# SparkFun_Mega_Pro_Mini-3_3V.net
KiCad netlist of a schematic drawn in EAGLE
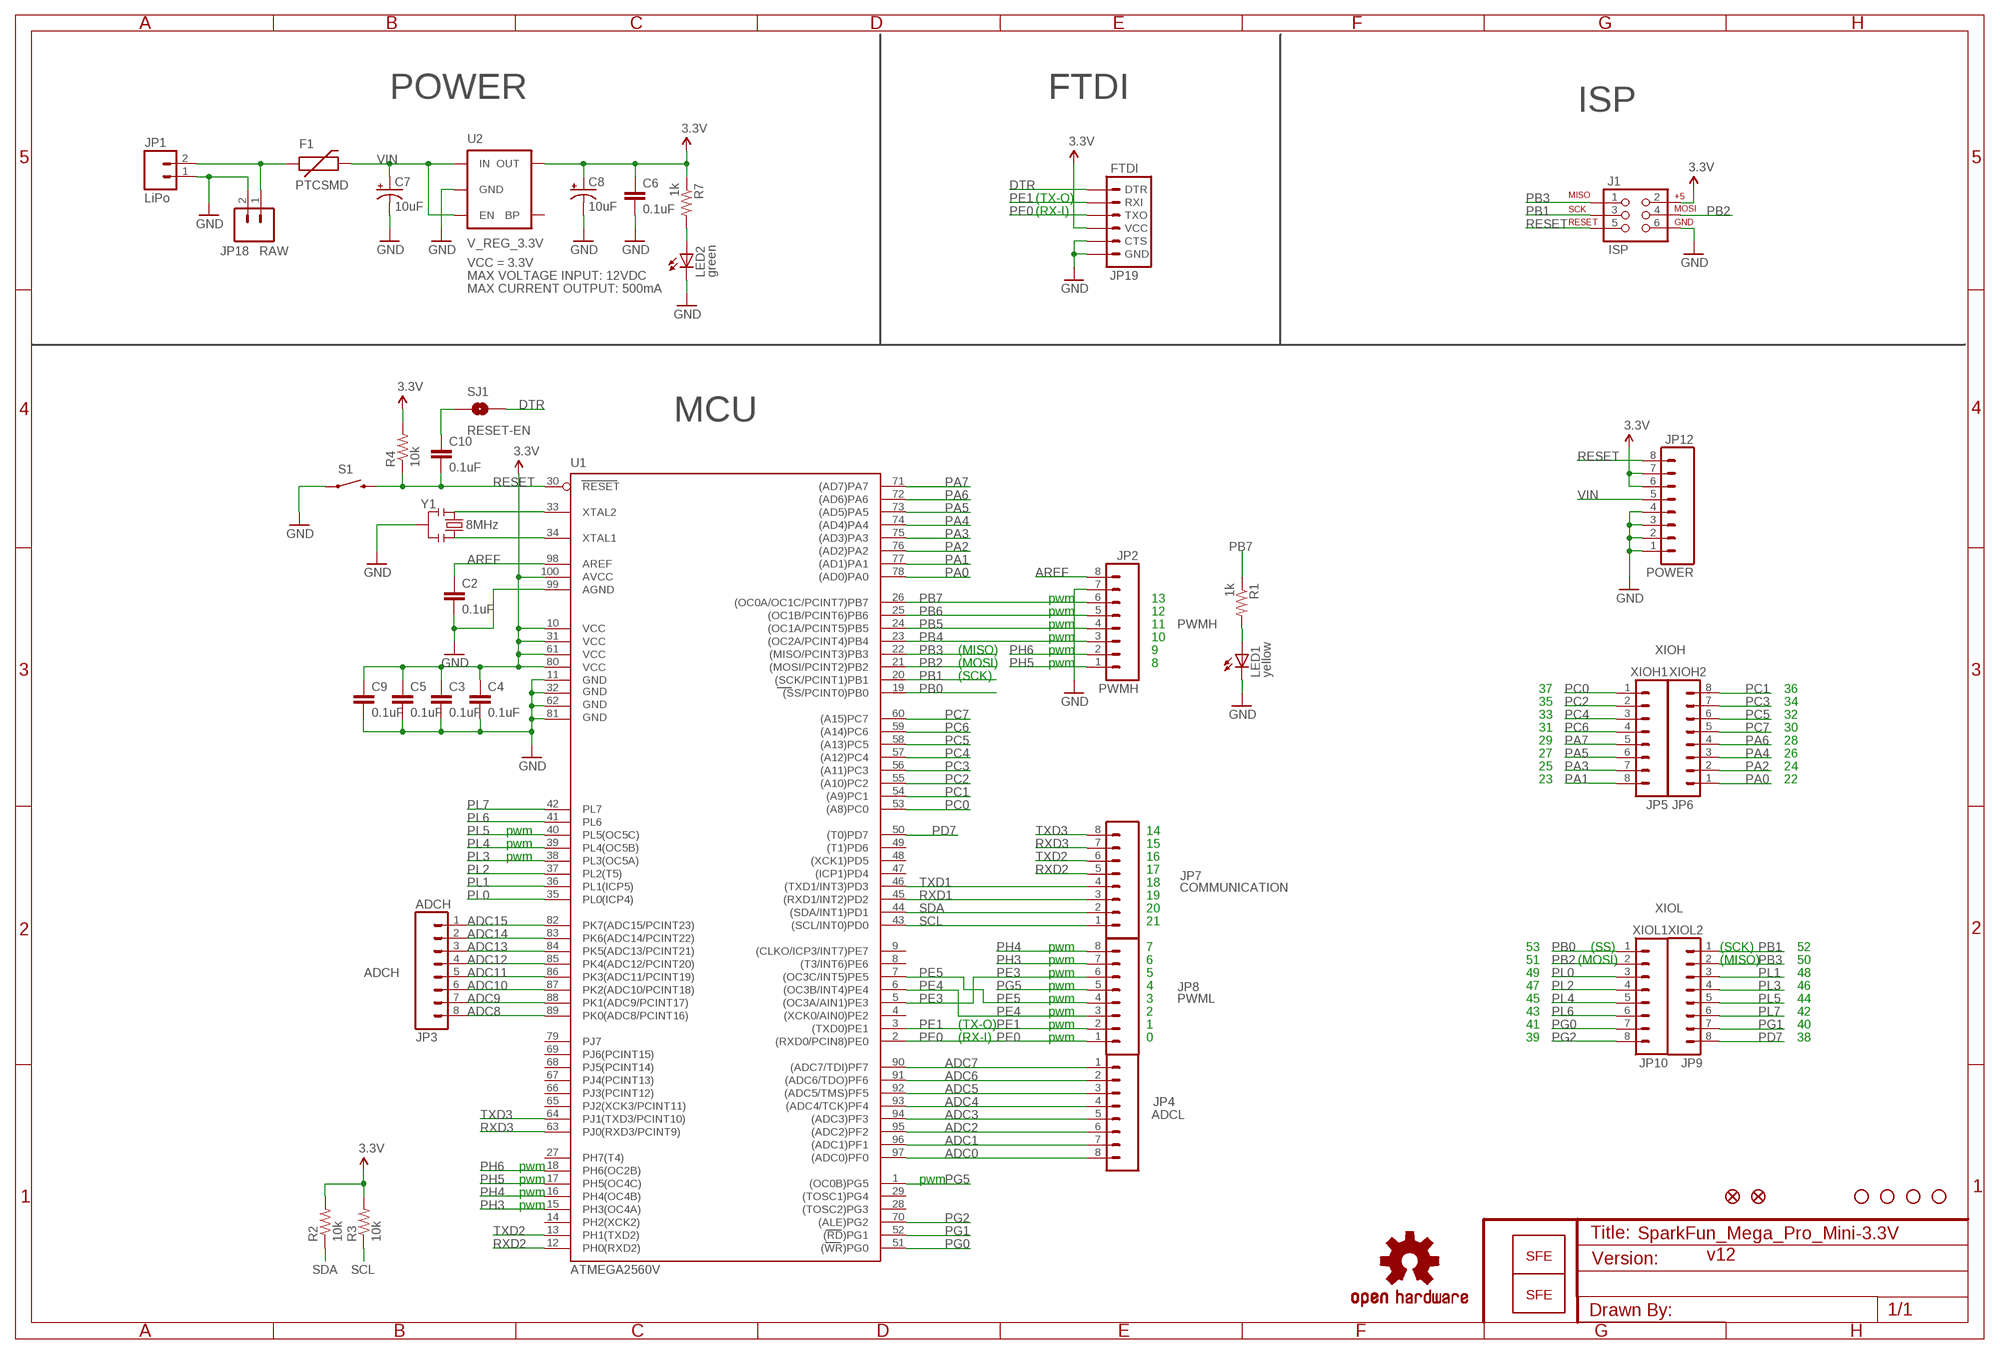
[diagram p0: schematic, sheet 1]

(export (version "E")
  (design (tool "Eeschema 10.0.6"))
  (components
    (comp (ref "C2")
      (value "0.1uF")
      (footprint "eagle-import:0402-CAP")
      (libsource (lib "eagle-import") (part "CAP0402-CAP"))
    )
    (comp (ref "C3")
      (value "0.1uF")
      (footprint "eagle-import:0402-CAP")
      (libsource (lib "eagle-import") (part "CAP0402-CAP"))
    )
    (comp (ref "C4")
      (value "0.1uF")
      (footprint "eagle-import:0402-CAP")
      (libsource (lib "eagle-import") (part "CAP0402-CAP"))
    )
    (comp (ref "C5")
      (value "0.1uF")
      (footprint "eagle-import:0402-CAP")
      (libsource (lib "eagle-import") (part "CAP0402-CAP"))
    )
    (comp (ref "C6")
      (value "0.1uF")
      (footprint "eagle-import:0402-CAP")
      (libsource (lib "eagle-import") (part "CAP0402-CAP"))
    )
    (comp (ref "C7")
      (value "10uF")
      (footprint "eagle-import:EIA3216")
      (libsource (lib "eagle-import") (part "CAP_POL1206"))
    )
    (comp (ref "C8")
      (value "10uF")
      (footprint "eagle-import:EIA3216")
      (libsource (lib "eagle-import") (part "CAP_POL1206"))
    )
    (comp (ref "C9")
      (value "0.1uF")
      (footprint "eagle-import:0402-CAP")
      (libsource (lib "eagle-import") (part "CAP0402-CAP"))
    )
    (comp (ref "C10")
      (value "0.1uF")
      (footprint "eagle-import:0402-CAP")
      (libsource (lib "eagle-import") (part "CAP0402-CAP"))
    )
    (comp (ref "F1")
      (value "PTCSMD")
      (footprint "eagle-import:PTC-1206")
      (libsource (lib "eagle-import") (part "PTCSMD"))
    )
    (comp (ref "J1")
      (value "ISP")
      (footprint "eagle-import:2X3")
      (libsource (lib "eagle-import") (part "AVR_SPI_PRG_6PTH"))
    )
    (comp (ref "JP1")
      (value "LiPo")
      (footprint "eagle-import:JST-2-SMD")
      (libsource (lib "eagle-import") (part "M02-JST-2MM-SMT"))
    )
    (comp (ref "JP2")
      (value "PWMH")
      (footprint "eagle-import:BM08B-SRSS-TB")
      (libsource (lib "eagle-import") (part "M08BM08B-SRSS-TB"))
    )
    (comp (ref "JP3")
      (value "ADCH")
      (footprint "eagle-import:BM08B-SRSS-TB")
      (libsource (lib "eagle-import") (part "M08BM08B-SRSS-TB"))
    )
    (comp (ref "JP4")
      (value "ADCL")
      (footprint "eagle-import:BM08B-SRSS-TB")
      (libsource (lib "eagle-import") (part "M08BM08B-SRSS-TB"))
    )
    (comp (ref "JP5")
      (value "XIOH1")
      (footprint "eagle-import:BM08B-SRSS-TB")
      (libsource (lib "eagle-import") (part "M08BM08B-SRSS-TB"))
    )
    (comp (ref "JP6")
      (value "XIOH2")
      (footprint "eagle-import:BM08B-SRSS-TB")
      (libsource (lib "eagle-import") (part "M08BM08B-SRSS-TB"))
    )
    (comp (ref "JP7")
      (value "COMM")
      (footprint "eagle-import:BM08B-SRSS-TB")
      (libsource (lib "eagle-import") (part "M08BM08B-SRSS-TB"))
    )
    (comp (ref "JP8")
      (value "PWML")
      (footprint "eagle-import:BM08B-SRSS-TB")
      (libsource (lib "eagle-import") (part "M08BM08B-SRSS-TB"))
    )
    (comp (ref "JP9")
      (value "XIOL2")
      (footprint "eagle-import:BM08B-SRSS-TB")
      (libsource (lib "eagle-import") (part "M08BM08B-SRSS-TB"))
    )
    (comp (ref "JP10")
      (value "XIOL1")
      (footprint "eagle-import:BM08B-SRSS-TB")
      (libsource (lib "eagle-import") (part "M08BM08B-SRSS-TB"))
    )
    (comp (ref "JP11")
      (value "STAND-OFF")
      (footprint "eagle-import:STAND-OFF")
      (libsource (lib "eagle-import") (part "STAND-OFF"))
    )
    (comp (ref "JP12")
      (value "POWER")
      (footprint "eagle-import:BM08B-SRSS-TB")
      (libsource (lib "eagle-import") (part "M08BM08B-SRSS-TB"))
    )
    (comp (ref "JP13")
      (value "STAND-OFF")
      (footprint "eagle-import:STAND-OFF")
      (libsource (lib "eagle-import") (part "STAND-OFF"))
    )
    (comp (ref "JP14")
      (value "STAND-OFF")
      (footprint "eagle-import:STAND-OFF")
      (libsource (lib "eagle-import") (part "STAND-OFF"))
    )
    (comp (ref "JP15")
      (value "STAND-OFF")
      (footprint "eagle-import:STAND-OFF")
      (libsource (lib "eagle-import") (part "STAND-OFF"))
    )
    (comp (ref "JP16")
      (value "LOGO-SFENEW")
      (footprint "eagle-import:SFE-NEW-WEBLOGO")
      (libsource (lib "eagle-import") (part "LOGO-SFENEW"))
    )
    (comp (ref "JP17")
      (value "LOGO-SFESK")
      (footprint "eagle-import:SFE-LOGO-FLAME")
      (libsource (lib "eagle-import") (part "LOGO-SFESK"))
    )
    (comp (ref "JP18")
      (value "RAW")
      (footprint "eagle-import:1X02")
      (libsource (lib "eagle-import") (part "M02PTH"))
    )
    (comp (ref "JP19")
      (value "FTDI")
      (footprint "eagle-import:1X06-SMD")
      (libsource (lib "eagle-import") (part "ARDUINO_SERIAL_PROGRAMSMD"))
    )
    (comp (ref "JP20")
      (value "FIDUCIAL1X2.5")
      (footprint "eagle-import:FIDUCIAL-1X2.5")
      (libsource (lib "eagle-import") (part "FIDUCIAL1X2.5"))
    )
    (comp (ref "JP21")
      (value "FIDUCIAL1X2.5")
      (footprint "eagle-import:FIDUCIAL-1X2.5")
      (libsource (lib "eagle-import") (part "FIDUCIAL1X2.5"))
    )
    (comp (ref "LED1")
      (value "yellow")
      (footprint "eagle-import:LED-0603")
      (libsource (lib "eagle-import") (part "LED0603"))
    )
    (comp (ref "LED2")
      (value "green")
      (footprint "eagle-import:LED-0603")
      (libsource (lib "eagle-import") (part "LED0603"))
    )
    (comp (ref "R1")
      (value "1k")
      (footprint "eagle-import:0402-RES")
      (libsource (lib "eagle-import") (part "RESISTOR0402-RES"))
    )
    (comp (ref "R2")
      (value "10k")
      (footprint "eagle-import:0402-RES")
      (libsource (lib "eagle-import") (part "RESISTOR0402-RES"))
    )
    (comp (ref "R3")
      (value "10k")
      (footprint "eagle-import:0402-RES")
      (libsource (lib "eagle-import") (part "RESISTOR0402-RES"))
    )
    (comp (ref "R4")
      (value "10k")
      (footprint "eagle-import:0402-RES")
      (libsource (lib "eagle-import") (part "RESISTOR0402-RES"))
    )
    (comp (ref "R7")
      (value "1k")
      (footprint "eagle-import:0402-RES")
      (libsource (lib "eagle-import") (part "RESISTOR0402-RES"))
    )
    (comp (ref "S1")
      (value "SWITCH-MOMENTARY-2SMD")
      (footprint "eagle-import:TACTILE_SWITCH_SMD")
      (libsource (lib "eagle-import") (part "SWITCH-MOMENTARY-2SMD"))
    )
    (comp (ref "SJ1")
      (value "RESET-EN")
      (footprint "eagle-import:SJ_2S")
      (libsource (lib "eagle-import") (part "SOLDERJUMPERNC"))
    )
    (comp (ref "U$9")
      (value "OSHW-LOGOL")
      (footprint "eagle-import:OSHW-LOGO-L")
      (libsource (lib "eagle-import") (part "OSHW-LOGOL"))
    )
    (comp (ref "U1")
      (value "ATMEGA2560AU")
      (footprint "eagle-import:TQFP100")
      (libsource (lib "eagle-import") (part "ATMEGA2560AU"))
    )
    (comp (ref "U2")
      (value "V_REG_3.3V")
      (footprint "eagle-import:SOT23-5")
      (libsource (lib "eagle-import") (part "V_REG_LDOSMD"))
    )
    (comp (ref "Y1")
      (value "RESONATORSMD")
      (footprint "eagle-import:RESONATOR-SMD")
      (libsource (lib "eagle-import") (part "RESONATORSMD"))
    )
  )
  (nets
    (net (code "1") (name "/ADC0") (class "Default")
      (node (ref "JP4") (pin "8") (pinfunction "8_8") (pintype "passive"))
      (node (ref "U1") (pin "97") (pinfunction "(ADC0)PF0_97") (pintype "bidirectional"))
    )
    (net (code "2") (name "/ADC1") (class "Default")
      (node (ref "JP4") (pin "7") (pinfunction "7_7") (pintype "passive"))
      (node (ref "U1") (pin "96") (pinfunction "(ADC1)PF1_96") (pintype "bidirectional"))
    )
    (net (code "3") (name "/ADC2") (class "Default")
      (node (ref "JP4") (pin "6") (pinfunction "6_6") (pintype "passive"))
      (node (ref "U1") (pin "95") (pinfunction "(ADC2)PF2_95") (pintype "bidirectional"))
    )
    (net (code "4") (name "/ADC3") (class "Default")
      (node (ref "JP4") (pin "5") (pinfunction "5_5") (pintype "passive"))
      (node (ref "U1") (pin "94") (pinfunction "(ADC3)PF3_94") (pintype "bidirectional"))
    )
    (net (code "5") (name "/ADC4") (class "Default")
      (node (ref "JP4") (pin "4") (pinfunction "4_4") (pintype "passive"))
      (node (ref "U1") (pin "93") (pinfunction "(ADC4/TCK)PF4_93") (pintype "bidirectional"))
    )
    (net (code "6") (name "/ADC5") (class "Default")
      (node (ref "JP4") (pin "3") (pinfunction "3_3") (pintype "passive"))
      (node (ref "U1") (pin "92") (pinfunction "(ADC5/TMS)PF5_92") (pintype "bidirectional"))
    )
    (net (code "7") (name "/ADC6") (class "Default")
      (node (ref "JP4") (pin "2") (pinfunction "2_2") (pintype "passive"))
      (node (ref "U1") (pin "91") (pinfunction "(ADC6/TDO)PF6_91") (pintype "bidirectional"))
    )
    (net (code "8") (name "/ADC7") (class "Default")
      (node (ref "JP4") (pin "1") (pinfunction "1_1") (pintype "passive"))
      (node (ref "U1") (pin "90") (pinfunction "(ADC7/TDI)PF7_90") (pintype "bidirectional"))
    )
    (net (code "9") (name "/ADC8") (class "Default")
      (node (ref "JP3") (pin "8") (pinfunction "8_8") (pintype "passive"))
      (node (ref "U1") (pin "89") (pinfunction "PK0(ADC8/PCINT16)_89") (pintype "bidirectional"))
    )
    (net (code "10") (name "/ADC9") (class "Default")
      (node (ref "JP3") (pin "7") (pinfunction "7_7") (pintype "passive"))
      (node (ref "U1") (pin "88") (pinfunction "PK1(ADC9/PCINT17)_88") (pintype "bidirectional"))
    )
    (net (code "11") (name "/ADC10") (class "Default")
      (node (ref "JP3") (pin "6") (pinfunction "6_6") (pintype "passive"))
      (node (ref "U1") (pin "87") (pinfunction "PK2(ADC10/PCINT18)_87") (pintype "bidirectional"))
    )
    (net (code "12") (name "/ADC11") (class "Default")
      (node (ref "JP3") (pin "5") (pinfunction "5_5") (pintype "passive"))
      (node (ref "U1") (pin "86") (pinfunction "PK3(ADC11/PCINT19)_86") (pintype "bidirectional"))
    )
    (net (code "13") (name "/ADC12") (class "Default")
      (node (ref "JP3") (pin "4") (pinfunction "4_4") (pintype "passive"))
      (node (ref "U1") (pin "85") (pinfunction "PK4(ADC12/PCINT20)_85") (pintype "bidirectional"))
    )
    (net (code "14") (name "/ADC13") (class "Default")
      (node (ref "JP3") (pin "3") (pinfunction "3_3") (pintype "passive"))
      (node (ref "U1") (pin "84") (pinfunction "PK5(ADC13/PCINT21)_84") (pintype "bidirectional"))
    )
    (net (code "15") (name "/ADC14") (class "Default")
      (node (ref "JP3") (pin "2") (pinfunction "2_2") (pintype "passive"))
      (node (ref "U1") (pin "83") (pinfunction "PK6(ADC14/PCINT22)_83") (pintype "bidirectional"))
    )
    (net (code "16") (name "/ADC15") (class "Default")
      (node (ref "JP3") (pin "1") (pinfunction "1_1") (pintype "passive"))
      (node (ref "U1") (pin "82") (pinfunction "PK7(ADC15/PCINT23)_82") (pintype "bidirectional"))
    )
    (net (code "17") (name "/AREF") (class "Default")
      (node (ref "C2") (pin "1") (pinfunction "1_1") (pintype "passive"))
      (node (ref "JP2") (pin "8") (pinfunction "8_8") (pintype "passive"))
      (node (ref "U1") (pin "98") (pinfunction "AREF_98") (pintype "bidirectional"))
    )
    (net (code "18") (name "/DTR") (class "Default")
      (node (ref "JP19") (pin "1") (pinfunction "DTR_1") (pintype "passive"))
      (node (ref "SJ1") (pin "2") (pinfunction "2_2") (pintype "passive"))
    )
    (net (code "19") (name "/PA0") (class "Default")
      (node (ref "JP6") (pin "1") (pinfunction "1_1") (pintype "passive"))
      (node (ref "U1") (pin "78") (pinfunction "(AD0)PA0_78") (pintype "bidirectional"))
    )
    (net (code "20") (name "/PA1") (class "Default")
      (node (ref "JP5") (pin "8") (pinfunction "8_8") (pintype "passive"))
      (node (ref "U1") (pin "77") (pinfunction "(AD1)PA1_77") (pintype "bidirectional"))
    )
    (net (code "21") (name "/PA2") (class "Default")
      (node (ref "JP6") (pin "2") (pinfunction "2_2") (pintype "passive"))
      (node (ref "U1") (pin "76") (pinfunction "(AD2)PA2_76") (pintype "bidirectional"))
    )
    (net (code "22") (name "/PA3") (class "Default")
      (node (ref "JP5") (pin "7") (pinfunction "7_7") (pintype "passive"))
      (node (ref "U1") (pin "75") (pinfunction "(AD3)PA3_75") (pintype "bidirectional"))
    )
    (net (code "23") (name "/PA4") (class "Default")
      (node (ref "JP6") (pin "3") (pinfunction "3_3") (pintype "passive"))
      (node (ref "U1") (pin "74") (pinfunction "(AD4)PA4_74") (pintype "bidirectional"))
    )
    (net (code "24") (name "/PA5") (class "Default")
      (node (ref "JP5") (pin "6") (pinfunction "6_6") (pintype "passive"))
      (node (ref "U1") (pin "73") (pinfunction "(AD5)PA5_73") (pintype "bidirectional"))
    )
    (net (code "25") (name "/PA6") (class "Default")
      (node (ref "JP6") (pin "4") (pinfunction "4_4") (pintype "passive"))
      (node (ref "U1") (pin "72") (pinfunction "(AD6)PA6_72") (pintype "bidirectional"))
    )
    (net (code "26") (name "/PA7") (class "Default")
      (node (ref "JP5") (pin "5") (pinfunction "5_5") (pintype "passive"))
      (node (ref "U1") (pin "71") (pinfunction "(AD7)PA7_71") (pintype "bidirectional"))
    )
    (net (code "27") (name "/PB0") (class "Default")
      (node (ref "JP10") (pin "1") (pinfunction "1_1") (pintype "passive"))
      (node (ref "U1") (pin "19") (pinfunction "(SS/PCINT0)PB0_19") (pintype "bidirectional"))
    )
    (net (code "28") (name "/PB1") (class "Default")
      (node (ref "J1") (pin "3") (pinfunction "3_3") (pintype "passive"))
      (node (ref "JP9") (pin "1") (pinfunction "1_1") (pintype "passive"))
      (node (ref "U1") (pin "20") (pinfunction "(SCK/PCINT1)PB1_20") (pintype "bidirectional"))
    )
    (net (code "29") (name "/PB2") (class "Default")
      (node (ref "J1") (pin "4") (pinfunction "4_4") (pintype "passive"))
      (node (ref "JP10") (pin "2") (pinfunction "2_2") (pintype "passive"))
      (node (ref "U1") (pin "21") (pinfunction "(MOSI/PCINT2)PB2_21") (pintype "bidirectional"))
    )
    (net (code "30") (name "/PB3") (class "Default")
      (node (ref "J1") (pin "1") (pinfunction "1_1") (pintype "passive"))
      (node (ref "JP9") (pin "2") (pinfunction "2_2") (pintype "passive"))
      (node (ref "U1") (pin "22") (pinfunction "(MISO/PCINT3)PB3_22") (pintype "bidirectional"))
    )
    (net (code "31") (name "/PB4") (class "Default")
      (node (ref "JP2") (pin "3") (pinfunction "3_3") (pintype "passive"))
      (node (ref "U1") (pin "23") (pinfunction "(OC2A/PCINT4)PB4_23") (pintype "bidirectional"))
    )
    (net (code "32") (name "/PB5") (class "Default")
      (node (ref "JP2") (pin "4") (pinfunction "4_4") (pintype "passive"))
      (node (ref "U1") (pin "24") (pinfunction "(OC1A/PCINT5)PB5_24") (pintype "bidirectional"))
    )
    (net (code "33") (name "/PB6") (class "Default")
      (node (ref "JP2") (pin "5") (pinfunction "5_5") (pintype "passive"))
      (node (ref "U1") (pin "25") (pinfunction "(OC1B/PCINT6)PB6_25") (pintype "bidirectional"))
    )
    (net (code "34") (name "/PB7") (class "Default")
      (node (ref "JP2") (pin "6") (pinfunction "6_6") (pintype "passive"))
      (node (ref "R1") (pin "1") (pinfunction "1_1") (pintype "passive"))
      (node (ref "U1") (pin "26") (pinfunction "(OC0A/OC1C/PCINT7)PB7_26") (pintype "bidirectional"))
    )
    (net (code "35") (name "/PC0") (class "Default")
      (node (ref "JP5") (pin "1") (pinfunction "1_1") (pintype "passive"))
      (node (ref "U1") (pin "53") (pinfunction "(A8)PC0_53") (pintype "bidirectional"))
    )
    (net (code "36") (name "/PC1") (class "Default")
      (node (ref "JP6") (pin "8") (pinfunction "8_8") (pintype "passive"))
      (node (ref "U1") (pin "54") (pinfunction "(A9)PC1_54") (pintype "bidirectional"))
    )
    (net (code "37") (name "/PC2") (class "Default")
      (node (ref "JP5") (pin "2") (pinfunction "2_2") (pintype "passive"))
      (node (ref "U1") (pin "55") (pinfunction "(A10)PC2_55") (pintype "bidirectional"))
    )
    (net (code "38") (name "/PC3") (class "Default")
      (node (ref "JP6") (pin "7") (pinfunction "7_7") (pintype "passive"))
      (node (ref "U1") (pin "56") (pinfunction "(A11)PC3_56") (pintype "bidirectional"))
    )
    (net (code "39") (name "/PC4") (class "Default")
      (node (ref "JP5") (pin "3") (pinfunction "3_3") (pintype "passive"))
      (node (ref "U1") (pin "57") (pinfunction "(A12)PC4_57") (pintype "bidirectional"))
    )
    (net (code "40") (name "/PC5") (class "Default")
      (node (ref "JP6") (pin "6") (pinfunction "6_6") (pintype "passive"))
      (node (ref "U1") (pin "58") (pinfunction "(A13)PC5_58") (pintype "bidirectional"))
    )
    (net (code "41") (name "/PC6") (class "Default")
      (node (ref "JP5") (pin "4") (pinfunction "4_4") (pintype "passive"))
      (node (ref "U1") (pin "59") (pinfunction "(A14)PC6_59") (pintype "bidirectional"))
    )
    (net (code "42") (name "/PC7") (class "Default")
      (node (ref "JP6") (pin "5") (pinfunction "5_5") (pintype "passive"))
      (node (ref "U1") (pin "60") (pinfunction "(A15)PC7_60") (pintype "bidirectional"))
    )
    (net (code "43") (name "/PD7") (class "Default")
      (node (ref "JP9") (pin "8") (pinfunction "8_8") (pintype "passive"))
      (node (ref "U1") (pin "50") (pinfunction "(T0)PD7_50") (pintype "bidirectional"))
    )
    (net (code "44") (name "/PE0") (class "Default")
      (node (ref "JP19") (pin "3") (pinfunction "TXO_3") (pintype "passive"))
      (node (ref "JP8") (pin "1") (pinfunction "1_1") (pintype "passive"))
      (node (ref "U1") (pin "2") (pinfunction "(RXD0/PCIN8)PE0_2") (pintype "bidirectional"))
    )
    (net (code "45") (name "/PE1") (class "Default")
      (node (ref "JP19") (pin "2") (pinfunction "RXI_2") (pintype "passive"))
      (node (ref "JP8") (pin "2") (pinfunction "2_2") (pintype "passive"))
      (node (ref "U1") (pin "3") (pinfunction "(TXD0)PE1_3") (pintype "bidirectional"))
    )
    (net (code "46") (name "/PE3") (class "Default")
      (node (ref "JP8") (pin "6") (pinfunction "6_6") (pintype "passive"))
      (node (ref "U1") (pin "5") (pinfunction "(OC3A/AIN1)PE3_5") (pintype "bidirectional"))
    )
    (net (code "47") (name "/PE4") (class "Default")
      (node (ref "JP8") (pin "3") (pinfunction "3_3") (pintype "passive"))
      (node (ref "U1") (pin "6") (pinfunction "(OC3B/INT4)PE4_6") (pintype "bidirectional"))
    )
    (net (code "48") (name "/PE5") (class "Default")
      (node (ref "JP8") (pin "4") (pinfunction "4_4") (pintype "passive"))
      (node (ref "U1") (pin "7") (pinfunction "(OC3C/INT5)PE5_7") (pintype "bidirectional"))
    )
    (net (code "49") (name "/PG0") (class "Default")
      (node (ref "JP10") (pin "7") (pinfunction "7_7") (pintype "passive"))
      (node (ref "U1") (pin "51") (pinfunction "(WR)PG0_51") (pintype "bidirectional"))
    )
    (net (code "50") (name "/PG1") (class "Default")
      (node (ref "JP9") (pin "7") (pinfunction "7_7") (pintype "passive"))
      (node (ref "U1") (pin "52") (pinfunction "(RD)PG1_52") (pintype "bidirectional"))
    )
    (net (code "51") (name "/PG2") (class "Default")
      (node (ref "JP10") (pin "8") (pinfunction "8_8") (pintype "passive"))
      (node (ref "U1") (pin "70") (pinfunction "(ALE)PG2_70") (pintype "bidirectional"))
    )
    (net (code "52") (name "/PG5") (class "Default")
      (node (ref "JP8") (pin "5") (pinfunction "5_5") (pintype "passive"))
      (node (ref "U1") (pin "1") (pinfunction "(OC0B)PG5_1") (pintype "bidirectional"))
    )
    (net (code "53") (name "/PH3") (class "Default")
      (node (ref "JP8") (pin "7") (pinfunction "7_7") (pintype "passive"))
      (node (ref "U1") (pin "15") (pinfunction "PH3(OC4A)_15") (pintype "bidirectional"))
    )
    (net (code "54") (name "/PH4") (class "Default")
      (node (ref "JP8") (pin "8") (pinfunction "8_8") (pintype "passive"))
      (node (ref "U1") (pin "16") (pinfunction "PH4(OC4B)_16") (pintype "bidirectional"))
    )
    (net (code "55") (name "/PH5") (class "Default")
      (node (ref "JP2") (pin "1") (pinfunction "1_1") (pintype "passive"))
      (node (ref "U1") (pin "17") (pinfunction "PH5(OC4C)_17") (pintype "bidirectional"))
    )
    (net (code "56") (name "/PH6") (class "Default")
      (node (ref "JP2") (pin "2") (pinfunction "2_2") (pintype "passive"))
      (node (ref "U1") (pin "18") (pinfunction "PH6(OC2B)_18") (pintype "bidirectional"))
    )
    (net (code "57") (name "/PL0") (class "Default")
      (node (ref "JP10") (pin "3") (pinfunction "3_3") (pintype "passive"))
      (node (ref "U1") (pin "35") (pinfunction "PL0(ICP4)_35") (pintype "bidirectional"))
    )
    (net (code "58") (name "/PL1") (class "Default")
      (node (ref "JP9") (pin "3") (pinfunction "3_3") (pintype "passive"))
      (node (ref "U1") (pin "36") (pinfunction "PL1(ICP5)_36") (pintype "bidirectional"))
    )
    (net (code "59") (name "/PL2") (class "Default")
      (node (ref "JP10") (pin "4") (pinfunction "4_4") (pintype "passive"))
      (node (ref "U1") (pin "37") (pinfunction "PL2(T5)_37") (pintype "bidirectional"))
    )
    (net (code "60") (name "/PL3") (class "Default")
      (node (ref "JP9") (pin "4") (pinfunction "4_4") (pintype "passive"))
      (node (ref "U1") (pin "38") (pinfunction "PL3(OC5A)_38") (pintype "bidirectional"))
    )
    (net (code "61") (name "/PL4") (class "Default")
      (node (ref "JP10") (pin "5") (pinfunction "5_5") (pintype "passive"))
      (node (ref "U1") (pin "39") (pinfunction "PL4(OC5B)_39") (pintype "bidirectional"))
    )
    (net (code "62") (name "/PL5") (class "Default")
      (node (ref "JP9") (pin "5") (pinfunction "5_5") (pintype "passive"))
      (node (ref "U1") (pin "40") (pinfunction "PL5(OC5C)_40") (pintype "bidirectional"))
    )
    (net (code "63") (name "/PL6") (class "Default")
      (node (ref "JP10") (pin "6") (pinfunction "6_6") (pintype "passive"))
      (node (ref "U1") (pin "41") (pinfunction "PL6_41") (pintype "bidirectional"))
    )
    (net (code "64") (name "/PL7") (class "Default")
      (node (ref "JP9") (pin "6") (pinfunction "6_6") (pintype "passive"))
      (node (ref "U1") (pin "42") (pinfunction "PL7_42") (pintype "bidirectional"))
    )
    (net (code "65") (name "/RESET") (class "Default")
      (node (ref "C10") (pin "2") (pinfunction "2_2") (pintype "passive"))
      (node (ref "J1") (pin "5") (pinfunction "5_5") (pintype "passive"))
      (node (ref "JP12") (pin "8") (pinfunction "8_8") (pintype "passive"))
      (node (ref "R4") (pin "1") (pinfunction "1_1") (pintype "passive"))
      (node (ref "S1") (pin "3") (pinfunction "2_3") (pintype "passive"))
      (node (ref "U1") (pin "30") (pinfunction "RESET_30") (pintype "input"))
    )
    (net (code "66") (name "/RXD1") (class "Default")
      (node (ref "JP7") (pin "3") (pinfunction "3_3") (pintype "passive"))
      (node (ref "U1") (pin "45") (pinfunction "(RXD1/INT2)PD2_45") (pintype "bidirectional"))
    )
    (net (code "67") (name "/RXD2") (class "Default")
      (node (ref "JP7") (pin "5") (pinfunction "5_5") (pintype "passive"))
      (node (ref "U1") (pin "12") (pinfunction "PH0(RXD2)_12") (pintype "bidirectional"))
    )
    (net (code "68") (name "/RXD3") (class "Default")
      (node (ref "JP7") (pin "7") (pinfunction "7_7") (pintype "passive"))
      (node (ref "U1") (pin "63") (pinfunction "PJ0(RXD3/PCINT9)_63") (pintype "bidirectional"))
    )
    (net (code "69") (name "/SCL") (class "Default")
      (node (ref "JP7") (pin "1") (pinfunction "1_1") (pintype "passive"))
      (node (ref "R3") (pin "1") (pinfunction "1_1") (pintype "passive"))
      (node (ref "U1") (pin "43") (pinfunction "(SCL/INT0)PD0_43") (pintype "bidirectional"))
    )
    (net (code "70") (name "/SDA") (class "Default")
      (node (ref "JP7") (pin "2") (pinfunction "2_2") (pintype "passive"))
      (node (ref "R2") (pin "1") (pinfunction "1_1") (pintype "passive"))
      (node (ref "U1") (pin "44") (pinfunction "(SDA/INT1)PD1_44") (pintype "bidirectional"))
    )
    (net (code "71") (name "/TXD1") (class "Default")
      (node (ref "JP7") (pin "4") (pinfunction "4_4") (pintype "passive"))
      (node (ref "U1") (pin "46") (pinfunction "(TXD1/INT3)PD3_46") (pintype "bidirectional"))
    )
    (net (code "72") (name "/TXD2") (class "Default")
      (node (ref "JP7") (pin "6") (pinfunction "6_6") (pintype "passive"))
      (node (ref "U1") (pin "13") (pinfunction "PH1(TXD2)_13") (pintype "bidirectional"))
    )
    (net (code "73") (name "/TXD3") (class "Default")
      (node (ref "JP7") (pin "8") (pinfunction "8_8") (pintype "passive"))
      (node (ref "U1") (pin "64") (pinfunction "PJ1(TXD3/PCINT10)_64") (pintype "bidirectional"))
    )
    (net (code "74") (name "/VIN") (class "Default")
      (node (ref "C7") (pin "A") (pinfunction "+_A") (pintype "passive"))
      (node (ref "F1") (pin "2") (pinfunction "2_2") (pintype "bidirectional"))
      (node (ref "JP12") (pin "5") (pinfunction "5_5") (pintype "passive"))
      (node (ref "U2") (pin "1") (pinfunction "IN_1") (pintype "input"))
      (node (ref "U2") (pin "3") (pinfunction "EN_3") (pintype "input"))
    )
    (net (code "75") (name "3.3V") (class "Default")
      (node (ref "C3") (pin "1") (pinfunction "1_1") (pintype "passive"))
      (node (ref "C4") (pin "1") (pinfunction "1_1") (pintype "passive"))
      (node (ref "C5") (pin "1") (pinfunction "1_1") (pintype "passive"))
      (node (ref "C6") (pin "1") (pinfunction "1_1") (pintype "passive"))
      (node (ref "C8") (pin "A") (pinfunction "+_A") (pintype "passive"))
      (node (ref "C9") (pin "1") (pinfunction "1_1") (pintype "passive"))
      (node (ref "J1") (pin "2") (pinfunction "2_2") (pintype "passive"))
      (node (ref "JP12") (pin "6") (pinfunction "6_6") (pintype "passive"))
      (node (ref "JP12") (pin "7") (pinfunction "7_7") (pintype "passive"))
      (node (ref "JP19") (pin "4") (pinfunction "VCC_4") (pintype "passive"))
      (node (ref "R2") (pin "2") (pinfunction "2_2") (pintype "passive"))
      (node (ref "R3") (pin "2") (pinfunction "2_2") (pintype "passive"))
      (node (ref "R4") (pin "2") (pinfunction "2_2") (pintype "passive"))
      (node (ref "R7") (pin "1") (pinfunction "1_1") (pintype "passive"))
      (node (ref "U1") (pin "10") (pinfunction "VCC_10") (pintype "power_in"))
      (node (ref "U1") (pin "100") (pinfunction "AVCC_100") (pintype "power_in"))
      (node (ref "U1") (pin "31") (pinfunction "VCC1_31") (pintype "power_in"))
      (node (ref "U1") (pin "61") (pinfunction "VCC2_61") (pintype "power_in"))
      (node (ref "U1") (pin "80") (pinfunction "VCC3_80") (pintype "power_in"))
      (node (ref "U2") (pin "5") (pinfunction "OUT_5") (pintype "passive"))
    )
    (net (code "76") (name "GND") (class "Default")
      (node (ref "C2") (pin "2") (pinfunction "2_2") (pintype "passive"))
      (node (ref "C3") (pin "2") (pinfunction "2_2") (pintype "passive"))
      (node (ref "C4") (pin "2") (pinfunction "2_2") (pintype "passive"))
      (node (ref "C5") (pin "2") (pinfunction "2_2") (pintype "passive"))
      (node (ref "C6") (pin "2") (pinfunction "2_2") (pintype "passive"))
      (node (ref "C7") (pin "C") (pinfunction "-_C") (pintype "passive"))
      (node (ref "C8") (pin "C") (pinfunction "-_C") (pintype "passive"))
      (node (ref "C9") (pin "2") (pinfunction "2_2") (pintype "passive"))
      (node (ref "J1") (pin "6") (pinfunction "6_6") (pintype "passive"))
      (node (ref "JP1") (pin "1") (pinfunction "1_1") (pintype "passive"))
      (node (ref "JP12") (pin "1") (pinfunction "1_1") (pintype "passive"))
      (node (ref "JP12") (pin "2") (pinfunction "2_2") (pintype "passive"))
      (node (ref "JP12") (pin "3") (pinfunction "3_3") (pintype "passive"))
      (node (ref "JP12") (pin "4") (pinfunction "4_4") (pintype "passive"))
      (node (ref "JP18") (pin "2") (pinfunction "2_2") (pintype "passive"))
      (node (ref "JP19") (pin "5") (pinfunction "CTS_5") (pintype "passive"))
      (node (ref "JP19") (pin "6") (pinfunction "GND_6") (pintype "passive"))
      (node (ref "JP2") (pin "7") (pinfunction "7_7") (pintype "passive"))
      (node (ref "LED1") (pin "C") (pinfunction "C_C") (pintype "passive"))
      (node (ref "LED2") (pin "C") (pinfunction "C_C") (pintype "passive"))
      (node (ref "S1") (pin "1") (pinfunction "1_1") (pintype "passive"))
      (node (ref "U1") (pin "11") (pinfunction "GND_11") (pintype "power_in"))
      (node (ref "U1") (pin "32") (pinfunction "GND1_32") (pintype "power_in"))
      (node (ref "U1") (pin "62") (pinfunction "GND2_62") (pintype "power_in"))
      (node (ref "U1") (pin "81") (pinfunction "GND3_81") (pintype "power_in"))
      (node (ref "U1") (pin "99") (pinfunction "AGND_99") (pintype "power_in"))
      (node (ref "U2") (pin "2") (pinfunction "GND_2") (pintype "input"))
      (node (ref "Y1") (pin "2") (pinfunction "2_2") (pintype "passive"))
    )
    (net (code "77") (name "Net-(C10-Pad1)") (class "Default")
      (node (ref "C10") (pin "1") (pinfunction "1_1") (pintype "passive"))
      (node (ref "SJ1") (pin "1") (pinfunction "1_1") (pintype "passive"))
    )
    (net (code "78") (name "Net-(F1-Pad1)") (class "Default")
      (node (ref "F1") (pin "1") (pinfunction "1_1") (pintype "bidirectional"))
      (node (ref "JP1") (pin "2") (pinfunction "2_2") (pintype "passive"))
      (node (ref "JP18") (pin "1") (pinfunction "1_1") (pintype "passive"))
    )
    (net (code "79") (name "Net-(LED1-PadA)") (class "Default")
      (node (ref "LED1") (pin "A") (pinfunction "A_A") (pintype "passive"))
      (node (ref "R1") (pin "2") (pinfunction "2_2") (pintype "passive"))
    )
    (net (code "80") (name "Net-(LED2-PadA)") (class "Default")
      (node (ref "LED2") (pin "A") (pinfunction "A_A") (pintype "passive"))
      (node (ref "R7") (pin "2") (pinfunction "2_2") (pintype "passive"))
    )
    (net (code "81") (name "Net-(U1-XTAL1)") (class "Default")
      (node (ref "U1") (pin "34") (pinfunction "XTAL1_34") (pintype "input"))
      (node (ref "Y1") (pin "3") (pinfunction "3_3") (pintype "passive"))
    )
    (net (code "82") (name "Net-(U1-XTAL2)") (class "Default")
      (node (ref "U1") (pin "33") (pinfunction "XTAL2_33") (pintype "output"))
      (node (ref "Y1") (pin "1") (pinfunction "1_1") (pintype "passive"))
    )
    (net (code "83") (name "unconnected-(U1-(CLKO{slash}ICP3{slash}INT7)PE7-Pad9)") (class "Default")
      (node (ref "U1") (pin "9") (pinfunction "(CLKO/ICP3/INT7)PE7_9") (pintype "bidirectional"))
    )
    (net (code "84") (name "unconnected-(U1-(ICP1)PD4-Pad47)") (class "Default")
      (node (ref "U1") (pin "47") (pinfunction "(ICP1)PD4_47") (pintype "bidirectional"))
    )
    (net (code "85") (name "unconnected-(U1-(T1)PD6-Pad49)") (class "Default")
      (node (ref "U1") (pin "49") (pinfunction "(T1)PD6_49") (pintype "bidirectional"))
    )
    (net (code "86") (name "unconnected-(U1-(T3{slash}INT6)PE6-Pad8)") (class "Default")
      (node (ref "U1") (pin "8") (pinfunction "(T3/INT6)PE6_8") (pintype "bidirectional"))
    )
    (net (code "87") (name "unconnected-(U1-(TOSC1)PG4-Pad29)") (class "Default")
      (node (ref "U1") (pin "29") (pinfunction "(TOSC1)PG4_29") (pintype "bidirectional"))
    )
    (net (code "88") (name "unconnected-(U1-(TOSC2)PG3-Pad28)") (class "Default")
      (node (ref "U1") (pin "28") (pinfunction "(TOSC2)PG3_28") (pintype "bidirectional"))
    )
    (net (code "89") (name "unconnected-(U1-(XCK0{slash}AIN0)PE2-Pad4)") (class "Default")
      (node (ref "U1") (pin "4") (pinfunction "(XCK0/AIN0)PE2_4") (pintype "bidirectional"))
    )
    (net (code "90") (name "unconnected-(U1-(XCK1)PD5-Pad48)") (class "Default")
      (node (ref "U1") (pin "48") (pinfunction "(XCK1)PD5_48") (pintype "bidirectional"))
    )
    (net (code "91") (name "unconnected-(U1-PH2(XCK2)-Pad14)") (class "Default")
      (node (ref "U1") (pin "14") (pinfunction "PH2(XCK2)_14") (pintype "bidirectional"))
    )
    (net (code "92") (name "unconnected-(U1-PH7(T4)-Pad27)") (class "Default")
      (node (ref "U1") (pin "27") (pinfunction "PH7(T4)_27") (pintype "bidirectional"))
    )
    (net (code "93") (name "unconnected-(U1-PJ2(XCK3{slash}PCINT11)-Pad65)") (class "Default")
      (node (ref "U1") (pin "65") (pinfunction "PJ2(XCK3/PCINT11)_65") (pintype "bidirectional"))
    )
    (net (code "94") (name "unconnected-(U1-PJ3(PCINT12)-Pad66)") (class "Default")
      (node (ref "U1") (pin "66") (pinfunction "PJ3(PCINT12)_66") (pintype "bidirectional"))
    )
    (net (code "95") (name "unconnected-(U1-PJ4(PCINT13)-Pad67)") (class "Default")
      (node (ref "U1") (pin "67") (pinfunction "PJ4(PCINT13)_67") (pintype "bidirectional"))
    )
    (net (code "96") (name "unconnected-(U1-PJ5(PCINT14)-Pad68)") (class "Default")
      (node (ref "U1") (pin "68") (pinfunction "PJ5(PCINT14)_68") (pintype "bidirectional"))
    )
    (net (code "97") (name "unconnected-(U1-PJ6(PCINT15)-Pad69)") (class "Default")
      (node (ref "U1") (pin "69") (pinfunction "PJ6(PCINT15)_69") (pintype "bidirectional"))
    )
    (net (code "98") (name "unconnected-(U1-PJ7-Pad79)") (class "Default")
      (node (ref "U1") (pin "79") (pinfunction "PJ7_79") (pintype "bidirectional"))
    )
    (net (code "99") (name "unconnected-(U2-BP-Pad4)") (class "Default")
      (node (ref "U2") (pin "4") (pinfunction "BP_4") (pintype "input"))
    )
  )
)
